# PowCarbinBoard_MCU.net
KiCad netlist of a schematic drawn in Altium Designer
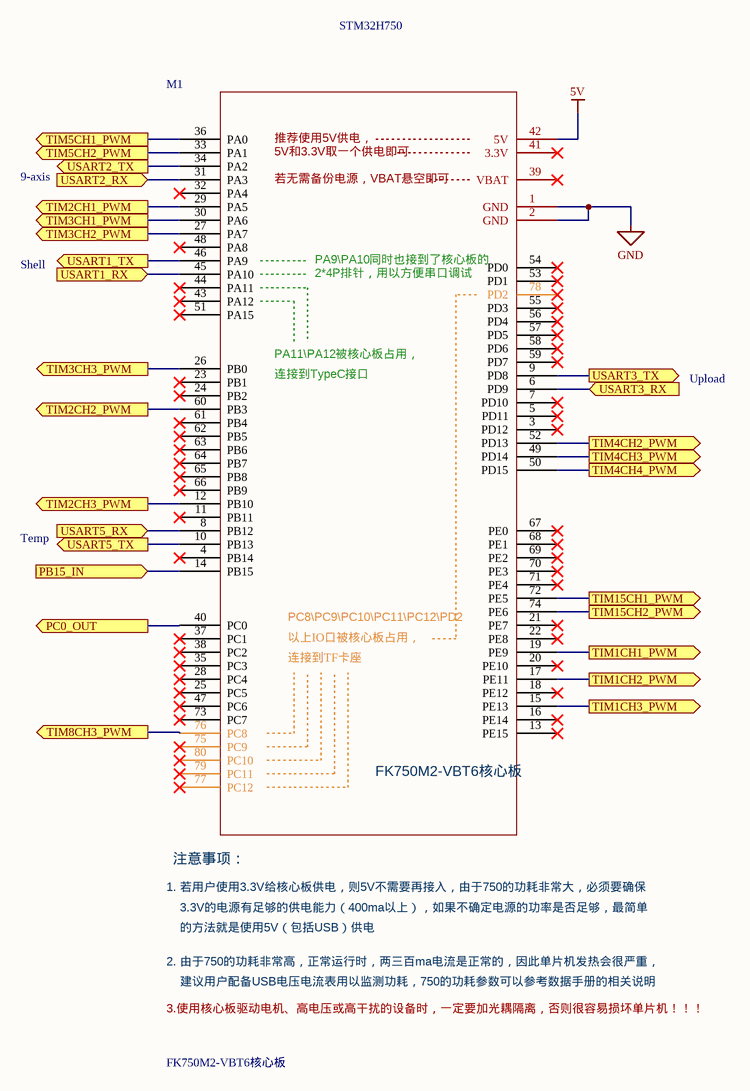
[diagram p0: PowCarbinBoard_MCU.SchDoc]

(export (version "E")
  (design (tool "Eeschema 10.0.6"))
  (components
    (comp (ref "M1")
      (value "FK750M2-VBT6核心板")
      (footprint "FK750M2-VBT6(精简版)")
      (libsource (lib "Schlib1") (part "FK750M2-VBT6"))
    )
  )
  (nets
    (net (code "1") (name "/PB15_IN") (class "Default")
      (node (ref "M1") (pin "14") (pinfunction "PB15_14") (pintype "passive"))
    )
    (net (code "2") (name "/PC0_OUT") (class "Default")
      (node (ref "M1") (pin "40") (pinfunction "PC0_40") (pintype "passive"))
    )
    (net (code "3") (name "/TIM1CH1_PWM") (class "Default")
      (node (ref "M1") (pin "19") (pinfunction "PE9_19") (pintype "passive"))
    )
    (net (code "4") (name "/TIM1CH2_PWM") (class "Default")
      (node (ref "M1") (pin "17") (pinfunction "PE11_17") (pintype "passive"))
    )
    (net (code "5") (name "/TIM1CH3_PWM") (class "Default")
      (node (ref "M1") (pin "15") (pinfunction "PE13_15") (pintype "passive"))
    )
    (net (code "6") (name "/TIM2CH1_PWM") (class "Default")
      (node (ref "M1") (pin "29") (pinfunction "PA5_29") (pintype "passive"))
    )
    (net (code "7") (name "/TIM2CH2_PWM") (class "Default")
      (node (ref "M1") (pin "60") (pinfunction "PB3_60") (pintype "passive"))
    )
    (net (code "8") (name "/TIM2CH3_PWM") (class "Default")
      (node (ref "M1") (pin "12") (pinfunction "PB10_12") (pintype "passive"))
    )
    (net (code "9") (name "/TIM3CH1_PWM") (class "Default")
      (node (ref "M1") (pin "30") (pinfunction "PA6_30") (pintype "passive"))
    )
    (net (code "10") (name "/TIM3CH2_PWM") (class "Default")
      (node (ref "M1") (pin "27") (pinfunction "PA7_27") (pintype "passive"))
    )
    (net (code "11") (name "/TIM3CH3_PWM") (class "Default")
      (node (ref "M1") (pin "26") (pinfunction "PB0_26") (pintype "passive"))
    )
    (net (code "12") (name "/TIM4CH2_PWM") (class "Default")
      (node (ref "M1") (pin "52") (pinfunction "PD13_52") (pintype "passive"))
    )
    (net (code "13") (name "/TIM4CH3_PWM") (class "Default")
      (node (ref "M1") (pin "49") (pinfunction "PD14_49") (pintype "passive"))
    )
    (net (code "14") (name "/TIM4CH4_PWM") (class "Default")
      (node (ref "M1") (pin "50") (pinfunction "PD15_50") (pintype "passive"))
    )
    (net (code "15") (name "/TIM5CH1_PWM") (class "Default")
      (node (ref "M1") (pin "36") (pinfunction "PA0_36") (pintype "passive"))
    )
    (net (code "16") (name "/TIM5CH2_PWM") (class "Default")
      (node (ref "M1") (pin "33") (pinfunction "PA1_33") (pintype "passive"))
    )
    (net (code "17") (name "/TIM8CH3_PWM") (class "Default")
      (node (ref "M1") (pin "76") (pinfunction "PC8_76") (pintype "passive"))
    )
    (net (code "18") (name "/TIM15CH1_PWM") (class "Default")
      (node (ref "M1") (pin "72") (pinfunction "PE5_72") (pintype "passive"))
    )
    (net (code "19") (name "/TIM15CH2_PWM") (class "Default")
      (node (ref "M1") (pin "74") (pinfunction "PE6_74") (pintype "passive"))
    )
    (net (code "20") (name "/USART1_RX") (class "Default")
      (node (ref "M1") (pin "45") (pinfunction "PA10_45") (pintype "passive"))
    )
    (net (code "21") (name "/USART1_TX") (class "Default")
      (node (ref "M1") (pin "46") (pinfunction "PA9_46") (pintype "passive"))
    )
    (net (code "22") (name "/USART2_RX") (class "Default")
      (node (ref "M1") (pin "31") (pinfunction "PA3_31") (pintype "passive"))
    )
    (net (code "23") (name "/USART2_TX") (class "Default")
      (node (ref "M1") (pin "34") (pinfunction "PA2_34") (pintype "passive"))
    )
    (net (code "24") (name "/USART3_RX") (class "Default")
      (node (ref "M1") (pin "6") (pinfunction "PD9_6") (pintype "passive"))
    )
    (net (code "25") (name "/USART3_TX") (class "Default")
      (node (ref "M1") (pin "9") (pinfunction "PD8_9") (pintype "passive"))
    )
    (net (code "26") (name "/USART5_RX") (class "Default")
      (node (ref "M1") (pin "8") (pinfunction "PB12_8") (pintype "passive"))
    )
    (net (code "27") (name "/USART5_TX") (class "Default")
      (node (ref "M1") (pin "10") (pinfunction "PB13_10") (pintype "passive"))
    )
    (net (code "28") (name "5V") (class "Default")
      (node (ref "M1") (pin "42") (pinfunction "5V_42") (pintype "passive"))
    )
    (net (code "29") (name "GND") (class "Default")
      (node (ref "M1") (pin "1") (pinfunction "GND_1") (pintype "passive"))
      (node (ref "M1") (pin "2") (pinfunction "GND_2") (pintype "passive"))
    )
    (net (code "30") (name "unconnected-(M1-3.3V-Pad41)") (class "Default")
      (node (ref "M1") (pin "41") (pinfunction "3.3V_41") (pintype "passive+no_connect"))
    )
    (net (code "31") (name "unconnected-(M1-PA4-Pad32)") (class "Default")
      (node (ref "M1") (pin "32") (pinfunction "PA4_32") (pintype "passive+no_connect"))
    )
    (net (code "32") (name "unconnected-(M1-PA8-Pad48)") (class "Default")
      (node (ref "M1") (pin "48") (pinfunction "PA8_48") (pintype "passive+no_connect"))
    )
    (net (code "33") (name "unconnected-(M1-PA11-Pad44)") (class "Default")
      (node (ref "M1") (pin "44") (pinfunction "PA11_44") (pintype "passive+no_connect"))
    )
    (net (code "34") (name "unconnected-(M1-PA12-Pad43)") (class "Default")
      (node (ref "M1") (pin "43") (pinfunction "PA12_43") (pintype "passive+no_connect"))
    )
    (net (code "35") (name "unconnected-(M1-PA15-Pad51)") (class "Default")
      (node (ref "M1") (pin "51") (pinfunction "PA15_51") (pintype "passive+no_connect"))
    )
    (net (code "36") (name "unconnected-(M1-PB1-Pad23)") (class "Default")
      (node (ref "M1") (pin "23") (pinfunction "PB1_23") (pintype "passive+no_connect"))
    )
    (net (code "37") (name "unconnected-(M1-PB2-Pad24)") (class "Default")
      (node (ref "M1") (pin "24") (pinfunction "PB2_24") (pintype "passive+no_connect"))
    )
    (net (code "38") (name "unconnected-(M1-PB4-Pad61)") (class "Default")
      (node (ref "M1") (pin "61") (pinfunction "PB4_61") (pintype "passive+no_connect"))
    )
    (net (code "39") (name "unconnected-(M1-PB5-Pad62)") (class "Default")
      (node (ref "M1") (pin "62") (pinfunction "PB5_62") (pintype "passive+no_connect"))
    )
    (net (code "40") (name "unconnected-(M1-PB6-Pad63)") (class "Default")
      (node (ref "M1") (pin "63") (pinfunction "PB6_63") (pintype "passive+no_connect"))
    )
    (net (code "41") (name "unconnected-(M1-PB7-Pad64)") (class "Default")
      (node (ref "M1") (pin "64") (pinfunction "PB7_64") (pintype "passive+no_connect"))
    )
    (net (code "42") (name "unconnected-(M1-PB8-Pad65)") (class "Default")
      (node (ref "M1") (pin "65") (pinfunction "PB8_65") (pintype "passive+no_connect"))
    )
    (net (code "43") (name "unconnected-(M1-PB9-Pad66)") (class "Default")
      (node (ref "M1") (pin "66") (pinfunction "PB9_66") (pintype "passive+no_connect"))
    )
    (net (code "44") (name "unconnected-(M1-PB11-Pad11)") (class "Default")
      (node (ref "M1") (pin "11") (pinfunction "PB11_11") (pintype "passive+no_connect"))
    )
    (net (code "45") (name "unconnected-(M1-PB14-Pad4)") (class "Default")
      (node (ref "M1") (pin "4") (pinfunction "PB14_4") (pintype "passive+no_connect"))
    )
    (net (code "46") (name "unconnected-(M1-PC1-Pad37)") (class "Default")
      (node (ref "M1") (pin "37") (pinfunction "PC1_37") (pintype "passive+no_connect"))
    )
    (net (code "47") (name "unconnected-(M1-PC2-Pad38)") (class "Default")
      (node (ref "M1") (pin "38") (pinfunction "PC2_38") (pintype "passive+no_connect"))
    )
    (net (code "48") (name "unconnected-(M1-PC3-Pad35)") (class "Default")
      (node (ref "M1") (pin "35") (pinfunction "PC3_35") (pintype "passive+no_connect"))
    )
    (net (code "49") (name "unconnected-(M1-PC4-Pad28)") (class "Default")
      (node (ref "M1") (pin "28") (pinfunction "PC4_28") (pintype "passive+no_connect"))
    )
    (net (code "50") (name "unconnected-(M1-PC5-Pad25)") (class "Default")
      (node (ref "M1") (pin "25") (pinfunction "PC5_25") (pintype "passive+no_connect"))
    )
    (net (code "51") (name "unconnected-(M1-PC6-Pad47)") (class "Default")
      (node (ref "M1") (pin "47") (pinfunction "PC6_47") (pintype "passive+no_connect"))
    )
    (net (code "52") (name "unconnected-(M1-PC7-Pad73)") (class "Default")
      (node (ref "M1") (pin "73") (pinfunction "PC7_73") (pintype "passive+no_connect"))
    )
    (net (code "53") (name "unconnected-(M1-PC9-Pad75)") (class "Default")
      (node (ref "M1") (pin "75") (pinfunction "PC9_75") (pintype "passive+no_connect"))
    )
    (net (code "54") (name "unconnected-(M1-PC10-Pad80)") (class "Default")
      (node (ref "M1") (pin "80") (pinfunction "PC10_80") (pintype "passive+no_connect"))
    )
    (net (code "55") (name "unconnected-(M1-PC11-Pad79)") (class "Default")
      (node (ref "M1") (pin "79") (pinfunction "PC11_79") (pintype "passive+no_connect"))
    )
    (net (code "56") (name "unconnected-(M1-PC12-Pad77)") (class "Default")
      (node (ref "M1") (pin "77") (pinfunction "PC12_77") (pintype "passive+no_connect"))
    )
    (net (code "57") (name "unconnected-(M1-PD0-Pad54)") (class "Default")
      (node (ref "M1") (pin "54") (pinfunction "PD0_54") (pintype "passive+no_connect"))
    )
    (net (code "58") (name "unconnected-(M1-PD1-Pad53)") (class "Default")
      (node (ref "M1") (pin "53") (pinfunction "PD1_53") (pintype "passive+no_connect"))
    )
    (net (code "59") (name "unconnected-(M1-PD2-Pad78)") (class "Default")
      (node (ref "M1") (pin "78") (pinfunction "PD2_78") (pintype "passive+no_connect"))
    )
    (net (code "60") (name "unconnected-(M1-PD3-Pad55)") (class "Default")
      (node (ref "M1") (pin "55") (pinfunction "PD3_55") (pintype "passive+no_connect"))
    )
    (net (code "61") (name "unconnected-(M1-PD4-Pad56)") (class "Default")
      (node (ref "M1") (pin "56") (pinfunction "PD4_56") (pintype "passive+no_connect"))
    )
    (net (code "62") (name "unconnected-(M1-PD5-Pad57)") (class "Default")
      (node (ref "M1") (pin "57") (pinfunction "PD5_57") (pintype "passive+no_connect"))
    )
    (net (code "63") (name "unconnected-(M1-PD6-Pad58)") (class "Default")
      (node (ref "M1") (pin "58") (pinfunction "PD6_58") (pintype "passive+no_connect"))
    )
    (net (code "64") (name "unconnected-(M1-PD7-Pad59)") (class "Default")
      (node (ref "M1") (pin "59") (pinfunction "PD7_59") (pintype "passive+no_connect"))
    )
    (net (code "65") (name "unconnected-(M1-PD10-Pad7)") (class "Default")
      (node (ref "M1") (pin "7") (pinfunction "PD10_7") (pintype "passive+no_connect"))
    )
    (net (code "66") (name "unconnected-(M1-PD11-Pad5)") (class "Default")
      (node (ref "M1") (pin "5") (pinfunction "PD11_5") (pintype "passive+no_connect"))
    )
    (net (code "67") (name "unconnected-(M1-PD12-Pad3)") (class "Default")
      (node (ref "M1") (pin "3") (pinfunction "PD12_3") (pintype "passive+no_connect"))
    )
    (net (code "68") (name "unconnected-(M1-PE0-Pad67)") (class "Default")
      (node (ref "M1") (pin "67") (pinfunction "PE0_67") (pintype "passive+no_connect"))
    )
    (net (code "69") (name "unconnected-(M1-PE1-Pad68)") (class "Default")
      (node (ref "M1") (pin "68") (pinfunction "PE1_68") (pintype "passive+no_connect"))
    )
    (net (code "70") (name "unconnected-(M1-PE2-Pad69)") (class "Default")
      (node (ref "M1") (pin "69") (pinfunction "PE2_69") (pintype "passive+no_connect"))
    )
    (net (code "71") (name "unconnected-(M1-PE3-Pad70)") (class "Default")
      (node (ref "M1") (pin "70") (pinfunction "PE3_70") (pintype "passive+no_connect"))
    )
    (net (code "72") (name "unconnected-(M1-PE4-Pad71)") (class "Default")
      (node (ref "M1") (pin "71") (pinfunction "PE4_71") (pintype "passive+no_connect"))
    )
    (net (code "73") (name "unconnected-(M1-PE7-Pad21)") (class "Default")
      (node (ref "M1") (pin "21") (pinfunction "PE7_21") (pintype "passive+no_connect"))
    )
    (net (code "74") (name "unconnected-(M1-PE8-Pad22)") (class "Default")
      (node (ref "M1") (pin "22") (pinfunction "PE8_22") (pintype "passive+no_connect"))
    )
    (net (code "75") (name "unconnected-(M1-PE10-Pad20)") (class "Default")
      (node (ref "M1") (pin "20") (pinfunction "PE10_20") (pintype "passive+no_connect"))
    )
    (net (code "76") (name "unconnected-(M1-PE12-Pad18)") (class "Default")
      (node (ref "M1") (pin "18") (pinfunction "PE12_18") (pintype "passive+no_connect"))
    )
    (net (code "77") (name "unconnected-(M1-PE14-Pad16)") (class "Default")
      (node (ref "M1") (pin "16") (pinfunction "PE14_16") (pintype "passive+no_connect"))
    )
    (net (code "78") (name "unconnected-(M1-PE15-Pad13)") (class "Default")
      (node (ref "M1") (pin "13") (pinfunction "PE15_13") (pintype "passive+no_connect"))
    )
    (net (code "79") (name "unconnected-(M1-VBAT-Pad39)") (class "Default")
      (node (ref "M1") (pin "39") (pinfunction "VBAT_39") (pintype "passive+no_connect"))
    )
  )
)
